# xor.net
KiCad netlist of a schematic drawn in EAGLE
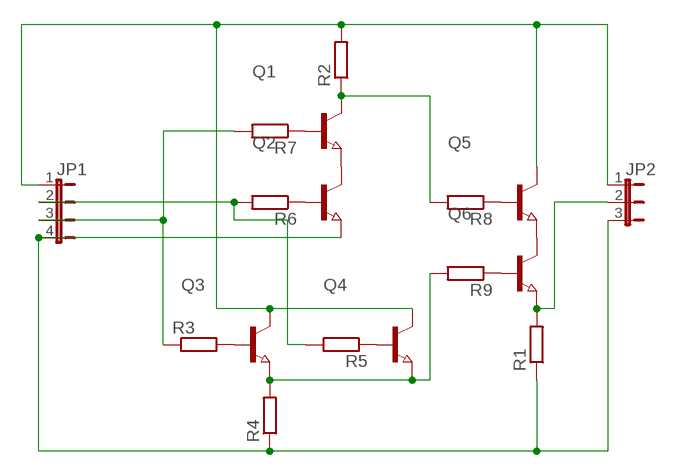
[diagram p0: schematic, sheet 1]

(export (version "E")
  (design (tool "Eeschema 10.0.6"))
  (components
    (comp (ref "JP1")
      (value "JP4E")
      (footprint "eagle-import:JP4")
      (libsource (lib "eagle-import") (part "JP4E"))
    )
    (comp (ref "JP2")
      (value "JP2W")
      (footprint "eagle-import:JP2W")
      (libsource (lib "eagle-import") (part "JP2W"))
    )
    (comp (ref "Q1")
      (value "NPN-TRANSISTOR_SOT23")
      (footprint "eagle-import:SOT23")
      (libsource (lib "eagle-import") (part "NPN-TRANSISTOR_SOT23"))
    )
    (comp (ref "Q2")
      (value "NPN-TRANSISTOR_SOT23")
      (footprint "eagle-import:SOT23")
      (libsource (lib "eagle-import") (part "NPN-TRANSISTOR_SOT23"))
    )
    (comp (ref "Q3")
      (value "NPN-TRANSISTOR_SOT23")
      (footprint "eagle-import:SOT23")
      (libsource (lib "eagle-import") (part "NPN-TRANSISTOR_SOT23"))
    )
    (comp (ref "Q4")
      (value "NPN-TRANSISTOR_SOT23")
      (footprint "eagle-import:SOT23")
      (libsource (lib "eagle-import") (part "NPN-TRANSISTOR_SOT23"))
    )
    (comp (ref "Q5")
      (value "NPN-TRANSISTOR_SOT23")
      (footprint "eagle-import:SOT23")
      (libsource (lib "eagle-import") (part "NPN-TRANSISTOR_SOT23"))
    )
    (comp (ref "Q6")
      (value "NPN-TRANSISTOR_SOT23")
      (footprint "eagle-import:SOT23")
      (libsource (lib "eagle-import") (part "NPN-TRANSISTOR_SOT23"))
    )
    (comp (ref "R1")
      (value "R-EU_R1206")
      (footprint "eagle-import:R1206")
      (libsource (lib "eagle-import") (part "R-EU_R1206"))
    )
    (comp (ref "R2")
      (value "R-EU_R1206")
      (footprint "eagle-import:R1206")
      (libsource (lib "eagle-import") (part "R-EU_R1206"))
    )
    (comp (ref "R3")
      (value "R-EU_R1206")
      (footprint "eagle-import:R1206")
      (libsource (lib "eagle-import") (part "R-EU_R1206"))
    )
    (comp (ref "R4")
      (value "R-EU_R1206")
      (footprint "eagle-import:R1206")
      (libsource (lib "eagle-import") (part "R-EU_R1206"))
    )
    (comp (ref "R5")
      (value "R-EU_R1206")
      (footprint "eagle-import:R1206")
      (libsource (lib "eagle-import") (part "R-EU_R1206"))
    )
    (comp (ref "R6")
      (value "R-EU_R1206")
      (footprint "eagle-import:R1206")
      (libsource (lib "eagle-import") (part "R-EU_R1206"))
    )
    (comp (ref "R7")
      (value "R-EU_R1206")
      (footprint "eagle-import:R1206")
      (libsource (lib "eagle-import") (part "R-EU_R1206"))
    )
    (comp (ref "R8")
      (value "R-EU_R1206")
      (footprint "eagle-import:R1206")
      (libsource (lib "eagle-import") (part "R-EU_R1206"))
    )
    (comp (ref "R9")
      (value "R-EU_R1206")
      (footprint "eagle-import:R1206")
      (libsource (lib "eagle-import") (part "R-EU_R1206"))
    )
  )
  (nets
    (net (code "1") (name "Net-(JP1-Pad2)") (class "Default")
      (node (ref "JP1") (pin "2") (pinfunction "2_2") (pintype "passive"))
      (node (ref "R5") (pin "2") (pinfunction "2_2") (pintype "passive"))
      (node (ref "R6") (pin "2") (pinfunction "2_2") (pintype "passive"))
    )
    (net (code "2") (name "Net-(JP1-Pad3)") (class "Default")
      (node (ref "JP1") (pin "3") (pinfunction "3_3") (pintype "passive"))
      (node (ref "R3") (pin "1") (pinfunction "1_1") (pintype "passive"))
      (node (ref "R7") (pin "2") (pinfunction "2_2") (pintype "passive"))
    )
    (net (code "3") (name "Net-(Q1-B)") (class "Default")
      (node (ref "Q1") (pin "1") (pinfunction "B_1") (pintype "passive"))
      (node (ref "R7") (pin "1") (pinfunction "1_1") (pintype "passive"))
    )
    (net (code "4") (name "Net-(Q1-C)") (class "Default")
      (node (ref "Q1") (pin "3") (pinfunction "C_3") (pintype "passive"))
      (node (ref "R2") (pin "1") (pinfunction "1_1") (pintype "passive"))
      (node (ref "R8") (pin "2") (pinfunction "2_2") (pintype "passive"))
    )
    (net (code "5") (name "Net-(Q1-E)") (class "Default")
      (node (ref "Q1") (pin "2") (pinfunction "E_2") (pintype "passive"))
      (node (ref "Q2") (pin "3") (pinfunction "C_3") (pintype "passive"))
    )
    (net (code "6") (name "Net-(Q2-B)") (class "Default")
      (node (ref "Q2") (pin "1") (pinfunction "B_1") (pintype "passive"))
      (node (ref "R6") (pin "1") (pinfunction "1_1") (pintype "passive"))
    )
    (net (code "7") (name "Net-(Q2-E)") (class "Default")
      (node (ref "JP1") (pin "4") (pinfunction "4_4") (pintype "passive"))
      (node (ref "JP2") (pin "3") (pinfunction "3_3") (pintype "passive"))
      (node (ref "Q2") (pin "2") (pinfunction "E_2") (pintype "passive"))
      (node (ref "R1") (pin "1") (pinfunction "1_1") (pintype "passive"))
      (node (ref "R4") (pin "1") (pinfunction "1_1") (pintype "passive"))
    )
    (net (code "8") (name "Net-(Q3-B)") (class "Default")
      (node (ref "Q3") (pin "1") (pinfunction "B_1") (pintype "passive"))
      (node (ref "R3") (pin "2") (pinfunction "2_2") (pintype "passive"))
    )
    (net (code "9") (name "Net-(Q3-C)") (class "Default")
      (node (ref "JP1") (pin "1") (pinfunction "1_1") (pintype "passive"))
      (node (ref "JP2") (pin "1") (pinfunction "1_1") (pintype "passive"))
      (node (ref "Q3") (pin "3") (pinfunction "C_3") (pintype "passive"))
      (node (ref "Q4") (pin "3") (pinfunction "C_3") (pintype "passive"))
      (node (ref "Q5") (pin "3") (pinfunction "C_3") (pintype "passive"))
      (node (ref "R2") (pin "2") (pinfunction "2_2") (pintype "passive"))
    )
    (net (code "10") (name "Net-(Q3-E)") (class "Default")
      (node (ref "Q3") (pin "2") (pinfunction "E_2") (pintype "passive"))
      (node (ref "Q4") (pin "2") (pinfunction "E_2") (pintype "passive"))
      (node (ref "R4") (pin "2") (pinfunction "2_2") (pintype "passive"))
      (node (ref "R9") (pin "2") (pinfunction "2_2") (pintype "passive"))
    )
    (net (code "11") (name "Net-(Q4-B)") (class "Default")
      (node (ref "Q4") (pin "1") (pinfunction "B_1") (pintype "passive"))
      (node (ref "R5") (pin "1") (pinfunction "1_1") (pintype "passive"))
    )
    (net (code "12") (name "Net-(Q5-B)") (class "Default")
      (node (ref "Q5") (pin "1") (pinfunction "B_1") (pintype "passive"))
      (node (ref "R8") (pin "1") (pinfunction "1_1") (pintype "passive"))
    )
    (net (code "13") (name "Net-(Q5-E)") (class "Default")
      (node (ref "Q5") (pin "2") (pinfunction "E_2") (pintype "passive"))
      (node (ref "Q6") (pin "3") (pinfunction "C_3") (pintype "passive"))
    )
    (net (code "14") (name "Net-(Q6-B)") (class "Default")
      (node (ref "Q6") (pin "1") (pinfunction "B_1") (pintype "passive"))
      (node (ref "R9") (pin "1") (pinfunction "1_1") (pintype "passive"))
    )
    (net (code "15") (name "Net-(Q6-E)") (class "Default")
      (node (ref "JP2") (pin "2") (pinfunction "2_2") (pintype "passive"))
      (node (ref "Q6") (pin "2") (pinfunction "E_2") (pintype "passive"))
      (node (ref "R1") (pin "2") (pinfunction "2_2") (pintype "passive"))
    )
  )
)
